# pH.net
KiCad netlist of a schematic drawn in EAGLE
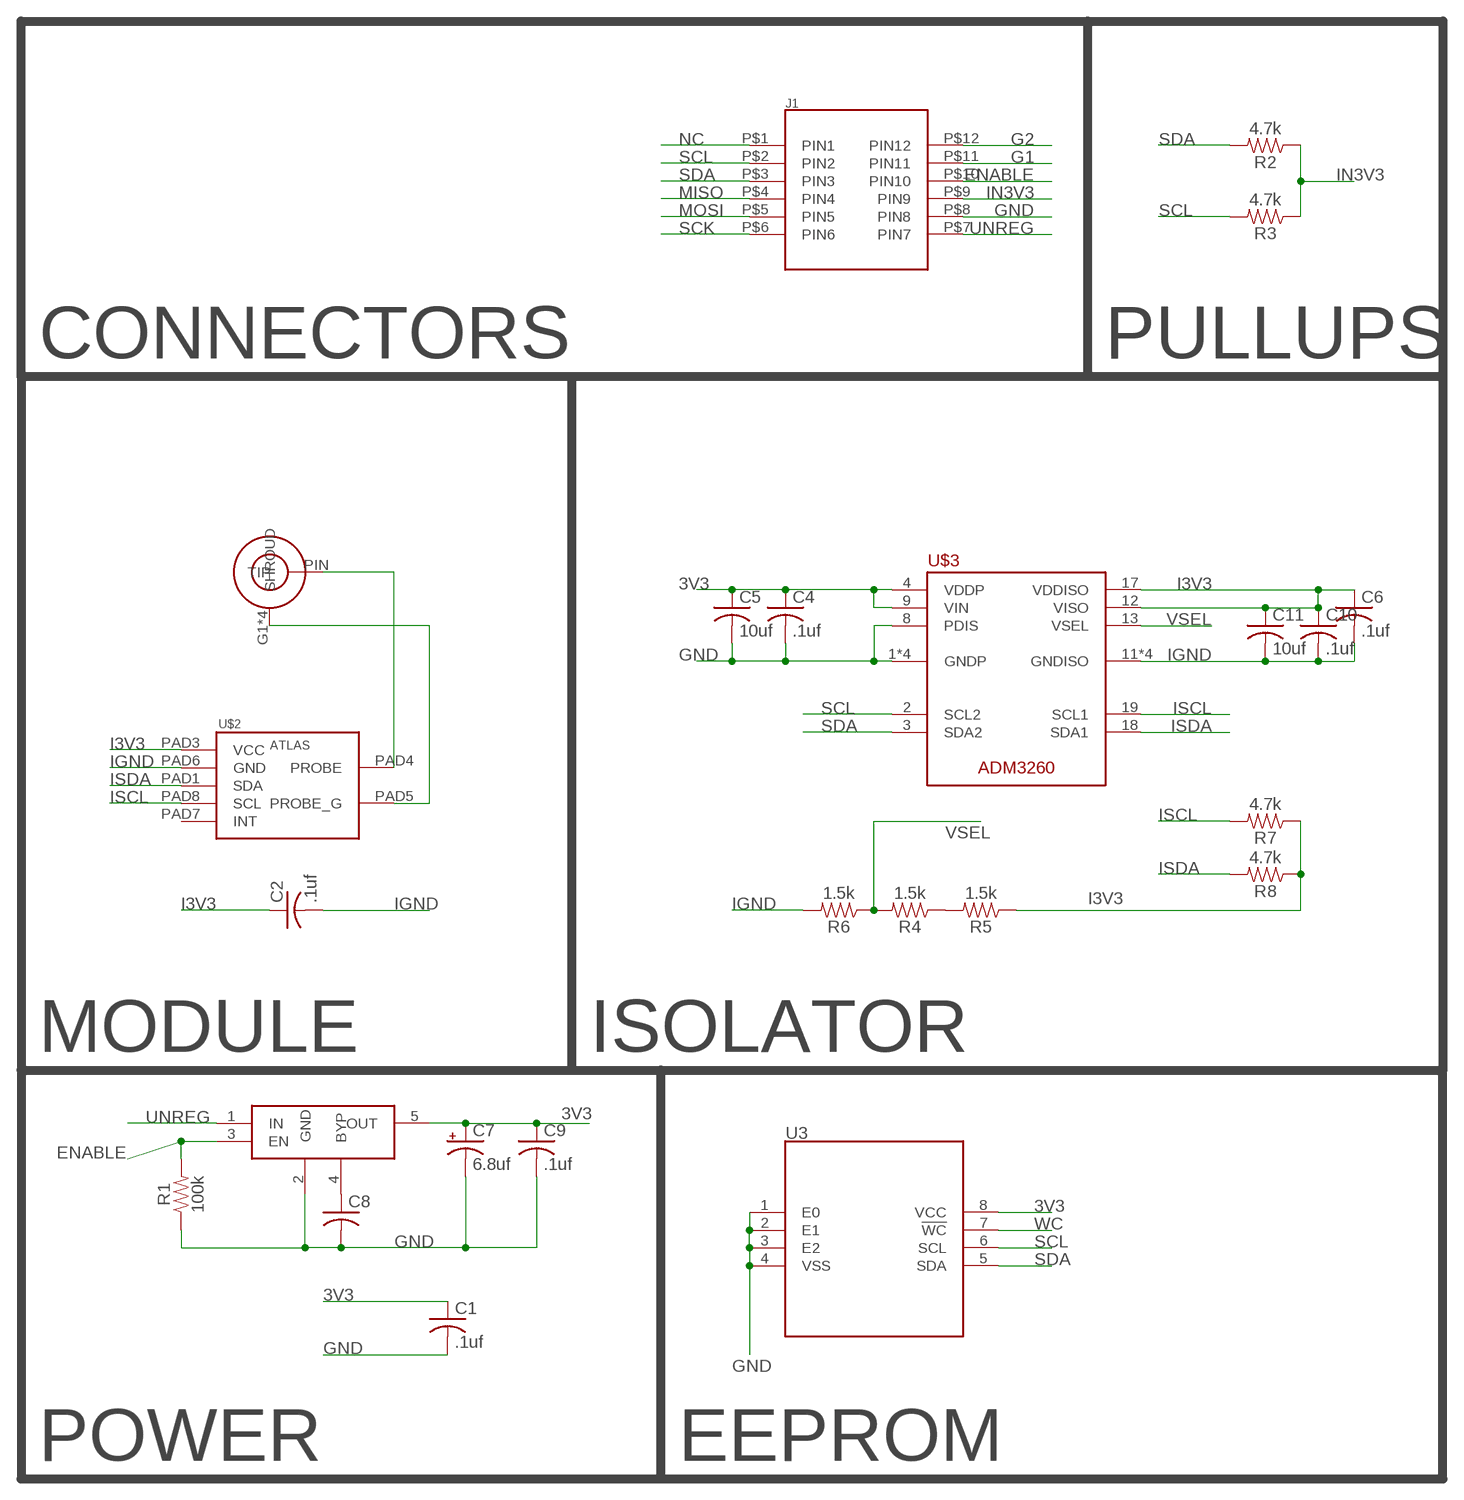
[diagram p0: schematic, sheet 1]

(export (version "E")
  (design (tool "Eeschema 10.0.6"))
  (components
    (comp (ref "C1")
      (value ".1uf")
      (footprint "eagle-import:C0603K")
      (libsource (lib "eagle-import") (part "C-USC0603K"))
    )
    (comp (ref "C2")
      (value ".1uf")
      (footprint "eagle-import:C0603K")
      (libsource (lib "eagle-import") (part "C-USC0603K"))
    )
    (comp (ref "C4")
      (value ".1uf")
      (footprint "eagle-import:C0603K")
      (libsource (lib "eagle-import") (part "C-USC0603K"))
    )
    (comp (ref "C5")
      (value "10uf")
      (footprint "eagle-import:C0603K")
      (libsource (lib "eagle-import") (part "C-USC0603K"))
    )
    (comp (ref "C6")
      (value ".1uf")
      (footprint "eagle-import:C0603K")
      (libsource (lib "eagle-import") (part "C-USC0603K"))
    )
    (comp (ref "C7")
      (value "6.8uf")
      (footprint "eagle-import:A_3216-18R")
      (libsource (lib "eagle-import") (part "CPOL-USA/3216-18R"))
    )
    (comp (ref "C8")
      (value "C-USC0603K")
      (footprint "eagle-import:C0603K")
      (libsource (lib "eagle-import") (part "C-USC0603K"))
    )
    (comp (ref "C9")
      (value ".1uf")
      (footprint "eagle-import:C0603K")
      (libsource (lib "eagle-import") (part "C-USC0603K"))
    )
    (comp (ref "C10")
      (value ".1uf")
      (footprint "eagle-import:C0603K")
      (libsource (lib "eagle-import") (part "C-USC0603K"))
    )
    (comp (ref "C11")
      (value "10uf")
      (footprint "eagle-import:C0603K")
      (libsource (lib "eagle-import") (part "C-USC0603K"))
    )
    (comp (ref "J1")
      (value "2X6-HEADERS")
      (footprint "eagle-import:M20-7810645")
      (libsource (lib "eagle-import") (part "2X6-HEADERS"))
    )
    (comp (ref "R1")
      (value "100k")
      (footprint "eagle-import:0603")
      (libsource (lib "eagle-import") (part "100KOHM-0603-1/10W-1%"))
    )
    (comp (ref "R2")
      (value "4.7k")
      (footprint "eagle-import:0603")
      (libsource (lib "eagle-import") (part "100KOHM-0603-1/10W-1%"))
    )
    (comp (ref "R3")
      (value "4.7k")
      (footprint "eagle-import:0603")
      (libsource (lib "eagle-import") (part "100KOHM-0603-1/10W-1%"))
    )
    (comp (ref "R4")
      (value "1.5k")
      (footprint "eagle-import:0603")
      (libsource (lib "eagle-import") (part "100KOHM-0603-1/10W-1%"))
    )
    (comp (ref "R5")
      (value "1.5k")
      (footprint "eagle-import:0603")
      (libsource (lib "eagle-import") (part "100KOHM-0603-1/10W-1%"))
    )
    (comp (ref "R6")
      (value "1.5k")
      (footprint "eagle-import:0603")
      (libsource (lib "eagle-import") (part "100KOHM-0603-1/10W-1%"))
    )
    (comp (ref "R7")
      (value "4.7k")
      (footprint "eagle-import:0603")
      (libsource (lib "eagle-import") (part "100KOHM-0603-1/10W-1%"))
    )
    (comp (ref "R8")
      (value "4.7k")
      (footprint "eagle-import:0603")
      (libsource (lib "eagle-import") (part "100KOHM-0603-1/10W-1%"))
    )
    (comp (ref "U$1")
      (value "5-1814832-1")
      (footprint "eagle-import:5-1814832-1")
      (libsource (lib "eagle-import") (part "5-1814832-1"))
    )
    (comp (ref "U$2")
      (value "ATLAS10P")
      (footprint "eagle-import:ATLAS-10P")
      (libsource (lib "eagle-import") (part "ATLAS10P"))
    )
    (comp (ref "U$3")
      (value "ADM3260")
      (footprint "eagle-import:SOP65P780X200-20")
      (libsource (lib "eagle-import") (part "ADM3260"))
    )
    (comp (ref "U$4")
      (value "MIC5219-3.3YM5-TR")
      (footprint "eagle-import:SOT95P280X145-5")
      (libsource (lib "eagle-import") (part "MIC5219-3.3YM5-TR"))
    )
    (comp (ref "U3")
      (value "M24C02-WMN6TP")
      (footprint "eagle-import:SOIC127P600X175-8")
      (libsource (lib "eagle-import") (part "M24C02-WMN6TP"))
    )
  )
  (nets
    (net (code "1") (name "/3V3") (class "Default")
      (node (ref "C1") (pin "1") (pinfunction "1_1") (pintype "passive"))
      (node (ref "C4") (pin "1") (pinfunction "1_1") (pintype "passive"))
      (node (ref "C5") (pin "1") (pinfunction "1_1") (pintype "passive"))
      (node (ref "C7") (pin "+") (pinfunction "+_+") (pintype "passive"))
      (node (ref "C9") (pin "1") (pinfunction "1_1") (pintype "passive"))
      (node (ref "U$3") (pin "4") (pinfunction "VDDP_4") (pintype "bidirectional"))
      (node (ref "U$3") (pin "9") (pinfunction "VIN_9") (pintype "bidirectional"))
      (node (ref "U$4") (pin "5") (pinfunction "OUT_5") (pintype "bidirectional"))
      (node (ref "U3") (pin "8") (pinfunction "VCC_8") (pintype "bidirectional"))
    )
    (net (code "2") (name "/ENABLE") (class "Default")
      (node (ref "J1") (pin "P$10") (pinfunction "PIN10_P$10") (pintype "bidirectional"))
      (node (ref "R1") (pin "2") (pinfunction "2_2") (pintype "passive"))
      (node (ref "U$4") (pin "3") (pinfunction "EN_3") (pintype "bidirectional"))
    )
    (net (code "3") (name "/G1") (class "Default")
      (node (ref "J1") (pin "P$11") (pinfunction "PIN11_P$11") (pintype "bidirectional"))
    )
    (net (code "4") (name "/G2") (class "Default")
      (node (ref "J1") (pin "P$12") (pinfunction "PIN12_P$12") (pintype "bidirectional"))
    )
    (net (code "5") (name "/GND") (class "Default")
      (node (ref "C1") (pin "2") (pinfunction "2_2") (pintype "passive"))
      (node (ref "C4") (pin "2") (pinfunction "2_2") (pintype "passive"))
      (node (ref "C5") (pin "2") (pinfunction "2_2") (pintype "passive"))
      (node (ref "C7") (pin "-") (pinfunction "-_-") (pintype "passive"))
      (node (ref "C8") (pin "2") (pinfunction "2_2") (pintype "passive"))
      (node (ref "C9") (pin "2") (pinfunction "2_2") (pintype "passive"))
      (node (ref "J1") (pin "P$8") (pinfunction "PIN8_P$8") (pintype "bidirectional"))
      (node (ref "R1") (pin "1") (pinfunction "1_1") (pintype "passive"))
      (node (ref "U$3") (pin "1") (pinfunction "GNDP_1") (pintype "bidirectional"))
      (node (ref "U$3") (pin "10") (pinfunction "GNDP_10") (pintype "bidirectional"))
      (node (ref "U$3") (pin "5") (pinfunction "GNDP_5") (pintype "bidirectional"))
      (node (ref "U$3") (pin "7") (pinfunction "GNDP_7") (pintype "bidirectional"))
      (node (ref "U$3") (pin "8") (pinfunction "PDIS_8") (pintype "bidirectional"))
      (node (ref "U$4") (pin "2") (pinfunction "GND_2") (pintype "bidirectional"))
      (node (ref "U3") (pin "1") (pinfunction "E0_1") (pintype "bidirectional"))
      (node (ref "U3") (pin "2") (pinfunction "E1_2") (pintype "bidirectional"))
      (node (ref "U3") (pin "3") (pinfunction "E2_3") (pintype "bidirectional"))
      (node (ref "U3") (pin "4") (pinfunction "VSS_4") (pintype "bidirectional"))
    )
    (net (code "6") (name "/I3V3") (class "Default")
      (node (ref "C10") (pin "1") (pinfunction "1_1") (pintype "passive"))
      (node (ref "C11") (pin "1") (pinfunction "1_1") (pintype "passive"))
      (node (ref "C2") (pin "1") (pinfunction "1_1") (pintype "passive"))
      (node (ref "C6") (pin "1") (pinfunction "1_1") (pintype "passive"))
      (node (ref "R5") (pin "1") (pinfunction "1_1") (pintype "passive"))
      (node (ref "R7") (pin "1") (pinfunction "1_1") (pintype "passive"))
      (node (ref "R8") (pin "1") (pinfunction "1_1") (pintype "passive"))
      (node (ref "U$2") (pin "PAD3") (pinfunction "VCC_PAD3") (pintype "bidirectional"))
      (node (ref "U$3") (pin "12") (pinfunction "VISO_12") (pintype "bidirectional"))
      (node (ref "U$3") (pin "17") (pinfunction "VDDISO_17") (pintype "bidirectional"))
    )
    (net (code "7") (name "/IGND") (class "Default")
      (node (ref "C10") (pin "2") (pinfunction "2_2") (pintype "passive"))
      (node (ref "C11") (pin "2") (pinfunction "2_2") (pintype "passive"))
      (node (ref "C2") (pin "2") (pinfunction "2_2") (pintype "passive"))
      (node (ref "C6") (pin "2") (pinfunction "2_2") (pintype "passive"))
      (node (ref "R6") (pin "2") (pinfunction "2_2") (pintype "passive"))
      (node (ref "U$2") (pin "PAD6") (pinfunction "GND_PAD6") (pintype "bidirectional"))
      (node (ref "U$3") (pin "11") (pinfunction "GNDISO_11") (pintype "bidirectional"))
      (node (ref "U$3") (pin "14") (pinfunction "GNDISO_14") (pintype "bidirectional"))
      (node (ref "U$3") (pin "16") (pinfunction "GNDISO_16") (pintype "bidirectional"))
      (node (ref "U$3") (pin "20") (pinfunction "GNDISO_20") (pintype "bidirectional"))
    )
    (net (code "8") (name "/IN3V3") (class "Default")
      (node (ref "J1") (pin "P$9") (pinfunction "PIN9_P$9") (pintype "bidirectional"))
      (node (ref "R2") (pin "1") (pinfunction "1_1") (pintype "passive"))
      (node (ref "R3") (pin "1") (pinfunction "1_1") (pintype "passive"))
    )
    (net (code "9") (name "/ISCL") (class "Default")
      (node (ref "R7") (pin "2") (pinfunction "2_2") (pintype "passive"))
      (node (ref "U$2") (pin "PAD8") (pinfunction "SCL_PAD8") (pintype "bidirectional"))
      (node (ref "U$3") (pin "19") (pinfunction "SCL1_19") (pintype "bidirectional"))
    )
    (net (code "10") (name "/ISDA") (class "Default")
      (node (ref "R8") (pin "2") (pinfunction "2_2") (pintype "passive"))
      (node (ref "U$2") (pin "PAD1") (pinfunction "SDA_PAD1") (pintype "bidirectional"))
      (node (ref "U$3") (pin "18") (pinfunction "SDA1_18") (pintype "bidirectional"))
    )
    (net (code "11") (name "/MISO") (class "Default")
      (node (ref "J1") (pin "P$4") (pinfunction "PIN4_P$4") (pintype "bidirectional"))
    )
    (net (code "12") (name "/MOSI") (class "Default")
      (node (ref "J1") (pin "P$5") (pinfunction "PIN5_P$5") (pintype "bidirectional"))
    )
    (net (code "13") (name "/NC") (class "Default")
      (node (ref "J1") (pin "P$1") (pinfunction "PIN1_P$1") (pintype "bidirectional"))
    )
    (net (code "14") (name "/SCK") (class "Default")
      (node (ref "J1") (pin "P$6") (pinfunction "PIN6_P$6") (pintype "bidirectional"))
    )
    (net (code "15") (name "/SCL") (class "Default")
      (node (ref "J1") (pin "P$2") (pinfunction "PIN2_P$2") (pintype "bidirectional"))
      (node (ref "R3") (pin "2") (pinfunction "2_2") (pintype "passive"))
      (node (ref "U$3") (pin "2") (pinfunction "SCL2_2") (pintype "bidirectional"))
      (node (ref "U3") (pin "6") (pinfunction "SCL_6") (pintype "bidirectional"))
    )
    (net (code "16") (name "/SDA") (class "Default")
      (node (ref "J1") (pin "P$3") (pinfunction "PIN3_P$3") (pintype "bidirectional"))
      (node (ref "R2") (pin "2") (pinfunction "2_2") (pintype "passive"))
      (node (ref "U$3") (pin "3") (pinfunction "SDA2_3") (pintype "bidirectional"))
      (node (ref "U3") (pin "5") (pinfunction "SDA_5") (pintype "bidirectional"))
    )
    (net (code "17") (name "/UNREG") (class "Default")
      (node (ref "J1") (pin "P$7") (pinfunction "PIN7_P$7") (pintype "bidirectional"))
      (node (ref "U$4") (pin "1") (pinfunction "IN_1") (pintype "bidirectional"))
    )
    (net (code "18") (name "/VSEL") (class "Default")
      (node (ref "R4") (pin "2") (pinfunction "2_2") (pintype "passive"))
      (node (ref "R6") (pin "1") (pinfunction "1_1") (pintype "passive"))
      (node (ref "U$3") (pin "13") (pinfunction "VSEL_13") (pintype "bidirectional"))
    )
    (net (code "19") (name "/WC") (class "Default")
      (node (ref "U3") (pin "7") (pinfunction "~{WC}_7") (pintype "bidirectional"))
    )
    (net (code "20") (name "Net-(R4-Pad1)") (class "Default")
      (node (ref "R4") (pin "1") (pinfunction "1_1") (pintype "passive"))
      (node (ref "R5") (pin "2") (pinfunction "2_2") (pintype "passive"))
    )
    (net (code "21") (name "Net-(U$1-TIP)") (class "Default")
      (node (ref "U$1") (pin "PIN") (pinfunction "TIP_PIN") (pintype "bidirectional"))
      (node (ref "U$2") (pin "PAD4") (pinfunction "PROBE_PAD4") (pintype "bidirectional"))
    )
    (net (code "22") (name "Net-(U$2-PROBE_G)") (class "Default")
      (node (ref "U$1") (pin "G1") (pinfunction "SHROUD_G1") (pintype "bidirectional"))
      (node (ref "U$1") (pin "G2") (pinfunction "SHROUD_G2") (pintype "bidirectional"))
      (node (ref "U$1") (pin "G3") (pinfunction "SHROUD_G3") (pintype "bidirectional"))
      (node (ref "U$1") (pin "G4") (pinfunction "SHROUD_G4") (pintype "bidirectional"))
      (node (ref "U$2") (pin "PAD5") (pinfunction "PROBE_G_PAD5") (pintype "bidirectional"))
    )
    (net (code "23") (name "Net-(U$4-BYP)") (class "Default")
      (node (ref "C8") (pin "1") (pinfunction "1_1") (pintype "passive"))
      (node (ref "U$4") (pin "4") (pinfunction "BYP_4") (pintype "bidirectional"))
    )
    (net (code "24") (name "unconnected-(U$2-INT-PadPAD7)") (class "Default")
      (node (ref "U$2") (pin "PAD7") (pinfunction "INT_PAD7") (pintype "bidirectional"))
    )
  )
)
